# SpinCoaterV3-AU_DC_Motor.net
KiCad netlist of a schematic drawn in EAGLE
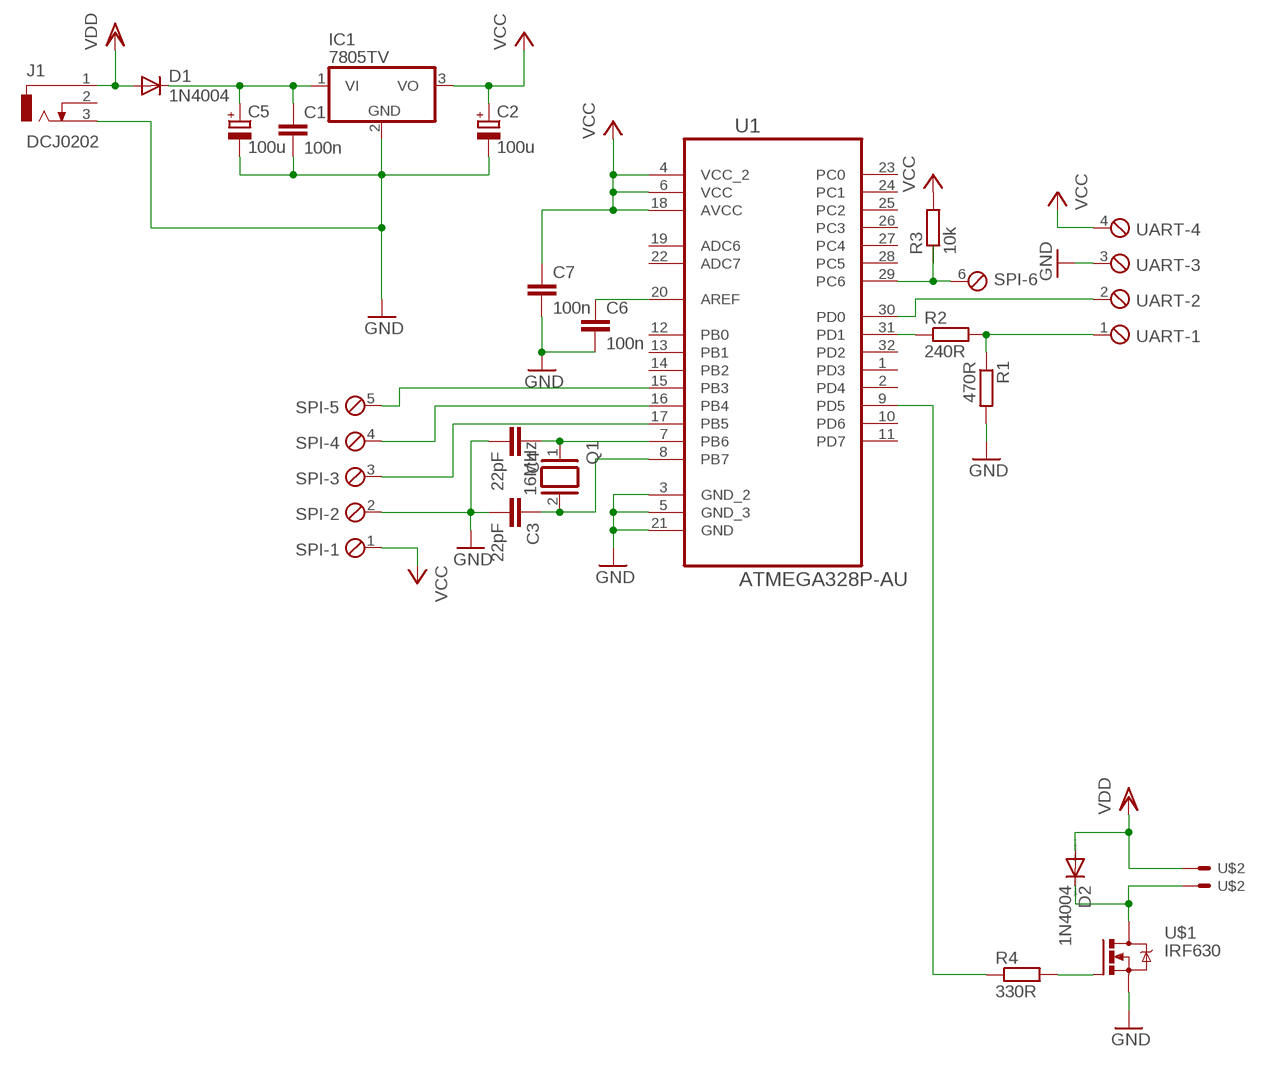
[diagram p0: schematic, sheet 1]

(export (version "E")
  (design (tool "Eeschema 10.0.6"))
  (components
    (comp (ref "C1")
      (value "100n")
      (footprint "eagle-import:C075-032X103")
      (libsource (lib "eagle-import") (part "C-EU075-032X103"))
    )
    (comp (ref "C2")
      (value "100u")
      (footprint "eagle-import:E2,5-6")
      (libsource (lib "eagle-import") (part "CPOL-EUE2.5-6"))
    )
    (comp (ref "C3")
      (value "22pF")
      (footprint "eagle-import:C050-030X075")
      (libsource (lib "eagle-import") (part "C-EU050-030X075"))
    )
    (comp (ref "C4")
      (value "22pF")
      (footprint "eagle-import:C050-030X075")
      (libsource (lib "eagle-import") (part "C-EU050-030X075"))
    )
    (comp (ref "C5")
      (value "100u")
      (footprint "eagle-import:E2,5-6")
      (libsource (lib "eagle-import") (part "CPOL-EUE2.5-6"))
    )
    (comp (ref "C6")
      (value "100n")
      (footprint "eagle-import:C075-032X103")
      (libsource (lib "eagle-import") (part "C-EU075-032X103"))
    )
    (comp (ref "C7")
      (value "100n")
      (footprint "eagle-import:C075-032X103")
      (libsource (lib "eagle-import") (part "C-EU075-032X103"))
    )
    (comp (ref "D1")
      (value "1N4004")
      (footprint "eagle-import:DO41-10")
      (libsource (lib "eagle-import") (part "diode-1_1N4004"))
    )
    (comp (ref "D2")
      (value "1N4004")
      (footprint "eagle-import:DO41-10")
      (libsource (lib "eagle-import") (part "1N4004"))
    )
    (comp (ref "IC1")
      (value "7805TV")
      (footprint "eagle-import:TO220V")
      (libsource (lib "eagle-import") (part "78TV05"))
    )
    (comp (ref "J1")
      (value "DCJ0202")
      (footprint "eagle-import:DCJ0202")
      (libsource (lib "eagle-import") (part "DCJ0202"))
    )
    (comp (ref "Q1")
      (value "16MHz")
      (footprint "eagle-import:QS")
      (libsource (lib "eagle-import") (part "XTAL/S"))
    )
    (comp (ref "R1")
      (value "470R")
      (footprint "eagle-import:0207_10")
      (libsource (lib "eagle-import") (part "R-EU_0207/10"))
    )
    (comp (ref "R2")
      (value "240R")
      (footprint "eagle-import:0207_10")
      (libsource (lib "eagle-import") (part "R-EU_0207/10"))
    )
    (comp (ref "R3")
      (value "10k")
      (footprint "eagle-import:0207_10")
      (libsource (lib "eagle-import") (part "R-EU_0207/10"))
    )
    (comp (ref "R4")
      (value "330R")
      (footprint "eagle-import:0207_10")
      (libsource (lib "eagle-import") (part "R-EU_0207/10"))
    )
    (comp (ref "SPI")
      (value "MPT6")
      (footprint "eagle-import:6POL254")
      (libsource (lib "eagle-import") (part "MPT6"))
    )
    (comp (ref "U$1")
      (value "IRF630")
      (footprint "eagle-import:TO-220BH")
      (libsource (lib "eagle-import") (part "IRF630"))
    )
    (comp (ref "U$2")
      (value "CON-MOTORDC")
      (footprint "eagle-import:CON-MOTOR")
      (libsource (lib "eagle-import") (part "CON-MOTORDC"))
    )
    (comp (ref "U1")
      (value "ATMEGA328P-AU")
      (footprint "eagle-import:QFP80P900X900X120-32N")
      (libsource (lib "eagle-import") (part "ATMEGA328P-AU"))
    )
    (comp (ref "UART")
      (value "MPT4")
      (footprint "eagle-import:4POL254")
      (libsource (lib "eagle-import") (part "MPT4"))
    )
  )
  (nets
    (net (code "1") (name "GND") (class "Default")
      (node (ref "C1") (pin "2") (pinfunction "2_2") (pintype "passive"))
      (node (ref "C2") (pin "-") (pinfunction "-_-") (pintype "passive"))
      (node (ref "C3") (pin "2") (pinfunction "2_2") (pintype "passive"))
      (node (ref "C4") (pin "2") (pinfunction "2_2") (pintype "passive"))
      (node (ref "C5") (pin "-") (pinfunction "-_-") (pintype "passive"))
      (node (ref "C6") (pin "2") (pinfunction "2_2") (pintype "passive"))
      (node (ref "C7") (pin "2") (pinfunction "2_2") (pintype "passive"))
      (node (ref "IC1") (pin "2") (pinfunction "GND_2") (pintype "passive"))
      (node (ref "J1") (pin "3") (pinfunction "3_3") (pintype "passive"))
      (node (ref "R1") (pin "2") (pinfunction "2_2") (pintype "passive"))
      (node (ref "SPI") (pin "2") (pinfunction "1_2") (pintype "passive"))
      (node (ref "U$1") (pin "S") (pinfunction "S_S") (pintype "passive"))
      (node (ref "U1") (pin "21") (pinfunction "GND_21") (pintype "passive"))
      (node (ref "U1") (pin "3") (pinfunction "GND_2_3") (pintype "passive"))
      (node (ref "U1") (pin "5") (pinfunction "GND_3_5") (pintype "passive"))
      (node (ref "UART") (pin "3") (pinfunction "1_3") (pintype "passive"))
    )
    (net (code "2") (name "Net-(IC1-VI)") (class "Default")
      (node (ref "C1") (pin "1") (pinfunction "1_1") (pintype "passive"))
      (node (ref "C5") (pin "+") (pinfunction "+_+") (pintype "passive"))
      (node (ref "D1") (pin "C") (pinfunction "C_C") (pintype "passive"))
      (node (ref "IC1") (pin "1") (pinfunction "VI_1") (pintype "input"))
    )
    (net (code "3") (name "Net-(R1-Pad1)") (class "Default")
      (node (ref "R1") (pin "1") (pinfunction "1_1") (pintype "passive"))
      (node (ref "R2") (pin "2") (pinfunction "2_2") (pintype "passive"))
      (node (ref "UART") (pin "1") (pinfunction "1_1") (pintype "passive"))
    )
    (net (code "4") (name "Net-(R4-Pad2)") (class "Default")
      (node (ref "R4") (pin "2") (pinfunction "2_2") (pintype "passive"))
      (node (ref "U$1") (pin "G") (pinfunction "G_G") (pintype "passive"))
    )
    (net (code "5") (name "Net-(SPIC-1)") (class "Default")
      (node (ref "SPI") (pin "3") (pinfunction "1_3") (pintype "passive"))
      (node (ref "U1") (pin "17") (pinfunction "PB5_17") (pintype "bidirectional"))
    )
    (net (code "6") (name "Net-(SPID-1)") (class "Default")
      (node (ref "SPI") (pin "4") (pinfunction "1_4") (pintype "passive"))
      (node (ref "U1") (pin "16") (pinfunction "PB4_16") (pintype "bidirectional"))
    )
    (net (code "7") (name "Net-(SPIE-1)") (class "Default")
      (node (ref "SPI") (pin "5") (pinfunction "1_5") (pintype "passive"))
      (node (ref "U1") (pin "15") (pinfunction "PB3_15") (pintype "bidirectional"))
    )
    (net (code "8") (name "Net-(SPIF-1)") (class "Default")
      (node (ref "R3") (pin "1") (pinfunction "1_1") (pintype "passive"))
      (node (ref "SPI") (pin "6") (pinfunction "1_6") (pintype "passive"))
      (node (ref "U1") (pin "29") (pinfunction "PC6_29") (pintype "bidirectional"))
    )
    (net (code "9") (name "Net-(U$2-S2)") (class "Default")
      (node (ref "D2") (pin "C") (pinfunction "C_C") (pintype "passive"))
      (node (ref "U$1") (pin "D") (pinfunction "D_D") (pintype "passive"))
      (node (ref "U$2") (pin "P$2") (pinfunction "S2_P$2") (pintype "passive"))
    )
    (net (code "10") (name "Net-(U1-AREF)") (class "Default")
      (node (ref "C6") (pin "1") (pinfunction "1_1") (pintype "passive"))
      (node (ref "U1") (pin "20") (pinfunction "AREF_20") (pintype "input"))
    )
    (net (code "11") (name "Net-(U1-PB6)") (class "Default")
      (node (ref "C4") (pin "1") (pinfunction "1_1") (pintype "passive"))
      (node (ref "Q1") (pin "1") (pinfunction "1_1") (pintype "passive"))
      (node (ref "U1") (pin "7") (pinfunction "PB6_7") (pintype "bidirectional"))
    )
    (net (code "12") (name "Net-(U1-PB7)") (class "Default")
      (node (ref "C3") (pin "1") (pinfunction "1_1") (pintype "passive"))
      (node (ref "Q1") (pin "2") (pinfunction "2_2") (pintype "passive"))
      (node (ref "U1") (pin "8") (pinfunction "PB7_8") (pintype "bidirectional"))
    )
    (net (code "13") (name "Net-(U1-PD0)") (class "Default")
      (node (ref "U1") (pin "30") (pinfunction "PD0_30") (pintype "bidirectional"))
      (node (ref "UART") (pin "2") (pinfunction "1_2") (pintype "passive"))
    )
    (net (code "14") (name "Net-(U1-PD1)") (class "Default")
      (node (ref "R2") (pin "1") (pinfunction "1_1") (pintype "passive"))
      (node (ref "U1") (pin "31") (pinfunction "PD1_31") (pintype "bidirectional"))
    )
    (net (code "15") (name "Net-(U1-PD5)") (class "Default")
      (node (ref "R4") (pin "1") (pinfunction "1_1") (pintype "passive"))
      (node (ref "U1") (pin "9") (pinfunction "PD5_9") (pintype "bidirectional"))
    )
    (net (code "16") (name "VCC") (class "Default")
      (node (ref "C2") (pin "+") (pinfunction "+_+") (pintype "passive"))
      (node (ref "C7") (pin "1") (pinfunction "1_1") (pintype "passive"))
      (node (ref "IC1") (pin "3") (pinfunction "VO_3") (pintype "passive"))
      (node (ref "R3") (pin "2") (pinfunction "2_2") (pintype "passive"))
      (node (ref "SPI") (pin "1") (pinfunction "1_1") (pintype "passive"))
      (node (ref "U1") (pin "18") (pinfunction "AVCC_18") (pintype "power_in"))
      (node (ref "U1") (pin "4") (pinfunction "VCC_2_4") (pintype "power_in"))
      (node (ref "U1") (pin "6") (pinfunction "VCC_6") (pintype "power_in"))
      (node (ref "UART") (pin "4") (pinfunction "1_4") (pintype "passive"))
    )
    (net (code "17") (name "VDD") (class "Default")
      (node (ref "D1") (pin "A") (pinfunction "A_A") (pintype "passive"))
      (node (ref "D2") (pin "A") (pinfunction "A_A") (pintype "passive"))
      (node (ref "J1") (pin "1") (pinfunction "1_1") (pintype "passive"))
      (node (ref "U$2") (pin "P$1") (pinfunction "S1_P$1") (pintype "passive"))
    )
    (net (code "18") (name "unconnected-(J1-Pad2)") (class "Default")
      (node (ref "J1") (pin "2") (pinfunction "2_2") (pintype "passive"))
    )
    (net (code "19") (name "unconnected-(U1-ADC6-Pad19)") (class "Default")
      (node (ref "U1") (pin "19") (pinfunction "ADC6_19") (pintype "input"))
    )
    (net (code "20") (name "unconnected-(U1-ADC7-Pad22)") (class "Default")
      (node (ref "U1") (pin "22") (pinfunction "ADC7_22") (pintype "input"))
    )
    (net (code "21") (name "unconnected-(U1-PB0-Pad12)") (class "Default")
      (node (ref "U1") (pin "12") (pinfunction "PB0_12") (pintype "bidirectional"))
    )
    (net (code "22") (name "unconnected-(U1-PB1-Pad13)") (class "Default")
      (node (ref "U1") (pin "13") (pinfunction "PB1_13") (pintype "bidirectional"))
    )
    (net (code "23") (name "unconnected-(U1-PB2-Pad14)") (class "Default")
      (node (ref "U1") (pin "14") (pinfunction "PB2_14") (pintype "bidirectional"))
    )
    (net (code "24") (name "unconnected-(U1-PC0-Pad23)") (class "Default")
      (node (ref "U1") (pin "23") (pinfunction "PC0_23") (pintype "bidirectional"))
    )
    (net (code "25") (name "unconnected-(U1-PC1-Pad24)") (class "Default")
      (node (ref "U1") (pin "24") (pinfunction "PC1_24") (pintype "bidirectional"))
    )
    (net (code "26") (name "unconnected-(U1-PC2-Pad25)") (class "Default")
      (node (ref "U1") (pin "25") (pinfunction "PC2_25") (pintype "bidirectional"))
    )
    (net (code "27") (name "unconnected-(U1-PC3-Pad26)") (class "Default")
      (node (ref "U1") (pin "26") (pinfunction "PC3_26") (pintype "bidirectional"))
    )
    (net (code "28") (name "unconnected-(U1-PC4-Pad27)") (class "Default")
      (node (ref "U1") (pin "27") (pinfunction "PC4_27") (pintype "bidirectional"))
    )
    (net (code "29") (name "unconnected-(U1-PC5-Pad28)") (class "Default")
      (node (ref "U1") (pin "28") (pinfunction "PC5_28") (pintype "bidirectional"))
    )
    (net (code "30") (name "unconnected-(U1-PD2-Pad32)") (class "Default")
      (node (ref "U1") (pin "32") (pinfunction "PD2_32") (pintype "bidirectional"))
    )
    (net (code "31") (name "unconnected-(U1-PD3-Pad1)") (class "Default")
      (node (ref "U1") (pin "1") (pinfunction "PD3_1") (pintype "bidirectional"))
    )
    (net (code "32") (name "unconnected-(U1-PD4-Pad2)") (class "Default")
      (node (ref "U1") (pin "2") (pinfunction "PD4_2") (pintype "bidirectional"))
    )
    (net (code "33") (name "unconnected-(U1-PD6-Pad10)") (class "Default")
      (node (ref "U1") (pin "10") (pinfunction "PD6_10") (pintype "bidirectional"))
    )
    (net (code "34") (name "unconnected-(U1-PD7-Pad11)") (class "Default")
      (node (ref "U1") (pin "11") (pinfunction "PD7_11") (pintype "bidirectional"))
    )
  )
)
